# RELAY6.net
KiCad netlist of a schematic drawn in Altium Designer
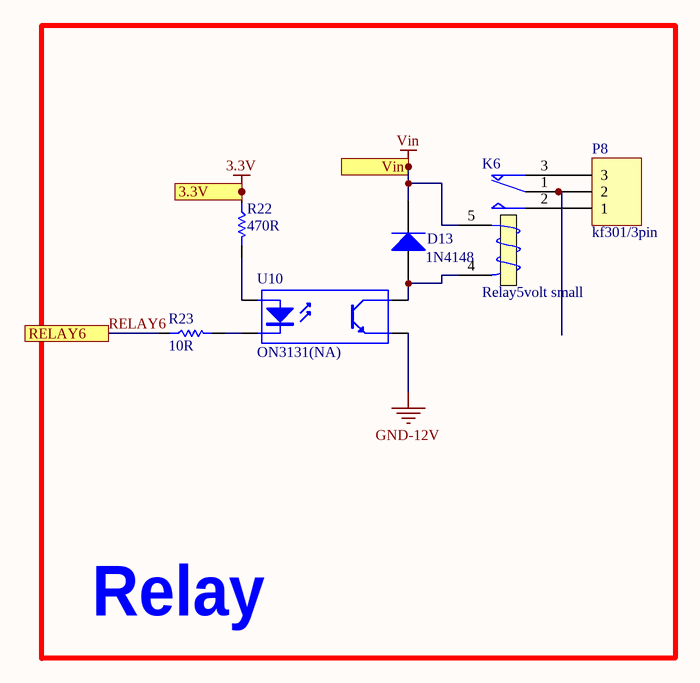
[diagram p0: RELAY6.SchDoc]

(export (version "E")
  (design (tool "Eeschema 10.0.6"))
  (components
    (comp (ref "D13")
      (value "1N4148")
      (footprint "sod123")
      (description "1 Amp General Purpose Rectifier")
      (fields (field (name "PUBLISHER") "Altium Limited"))
      (libsource (lib "Miscellaneous Devices") (part "Diode 1N4007"))
    )
    (comp (ref "K6")
      (value "Relay5volt small")
      (footprint "relay5_childern")
      (description "SPDT Relay")
      (fields (field (name "PUBLISHER") "Altium Limited"))
      (libsource (lib "FLIB") (part "Relay"))
    )
    (comp (ref "P8")
      (value "kf301/3pin")
      (footprint "Blue Connector 1*3 -kf301")
      (fields (field (name "PUBLISHER") "Altium Limited"))
      (libsource (lib "Miscellaneous Connectors") (part "Header 3"))
    )
    (comp (ref "R22")
      (value "470R")
      (footprint "0805/resistor")
      (description "Resistor")
      (fields (field (name "TOLERANCE") "5%") (field (name "POWER") "1/8 W"))
      (libsource (lib "skille") (part "Resistor"))
    )
    (comp (ref "R23")
      (value "10R")
      (footprint "0805/resistor")
      (description "Resistor")
      (fields (field (name "TOLERANCE") "5%") (field (name "POWER") "1/8 W"))
      (libsource (lib "skille") (part "Resistor"))
    )
    (comp (ref "U10")
      (value "ON3131(NA)")
      (footprint "OPTO_COUPLER")
      (description "4-Pin Phototransistor Optocoupler")
      (fields (field (name "PUBLISHER") "Altium Limited"))
      (libsource (lib "skille") (part "Optoisolator1"))
    )
  )
  (nets
    (net (code "1") (name "/RELAY6") (class "Default")
      (node (ref "R23") (pin "1") (pinfunction "1_1") (pintype "passive"))
    )
    (net (code "2") (name "3.3V") (class "Default")
      (node (ref "R22") (pin "1") (pinfunction "1_1") (pintype "passive"))
    )
    (net (code "3") (name "GND-12V") (class "Default")
      (node (ref "U10") (pin "3") (pinfunction "E_3") (pintype "passive"))
    )
    (net (code "4") (name "Net-(K6-COM)") (class "Default")
      (node (ref "K6") (pin "1") (pinfunction "COM_1") (pintype "passive"))
      (node (ref "P8") (pin "2") (pinfunction "2_2") (pintype "passive"))
    )
    (net (code "5") (name "Net-(K6-NO)") (class "Default")
      (node (ref "K6") (pin "2") (pinfunction "NO_2") (pintype "passive"))
      (node (ref "P8") (pin "1") (pinfunction "1_1") (pintype "passive"))
    )
    (net (code "6") (name "Net-(K6-T1)") (class "Default")
      (node (ref "K6") (pin "3") (pinfunction "T1_3") (pintype "passive"))
      (node (ref "P8") (pin "3") (pinfunction "3_3") (pintype "passive"))
    )
    (net (code "7") (name "Net-(K6-T2)") (class "Default")
      (node (ref "D13") (pin "A") (pinfunction "A_A") (pintype "passive"))
      (node (ref "K6") (pin "4") (pinfunction "T2_4") (pintype "passive"))
      (node (ref "U10") (pin "4") (pinfunction "C_4") (pintype "passive"))
    )
    (net (code "8") (name "Net-(U10-A)") (class "Default")
      (node (ref "R22") (pin "2") (pinfunction "2_2") (pintype "passive"))
      (node (ref "U10") (pin "1") (pinfunction "A_1") (pintype "passive"))
    )
    (net (code "9") (name "Net-(U10-K)") (class "Default")
      (node (ref "R23") (pin "2") (pinfunction "2_2") (pintype "passive"))
      (node (ref "U10") (pin "2") (pinfunction "K_2") (pintype "passive"))
    )
    (net (code "10") (name "Vin") (class "Default")
      (node (ref "D13") (pin "K") (pinfunction "K_K") (pintype "passive"))
      (node (ref "K6") (pin "5") (pinfunction "5_5") (pintype "passive"))
    )
  )
)
